# LB_BIT_i15_LIGHTTRIGGER-v02_rev1.net
KiCad netlist of a schematic drawn in EAGLE
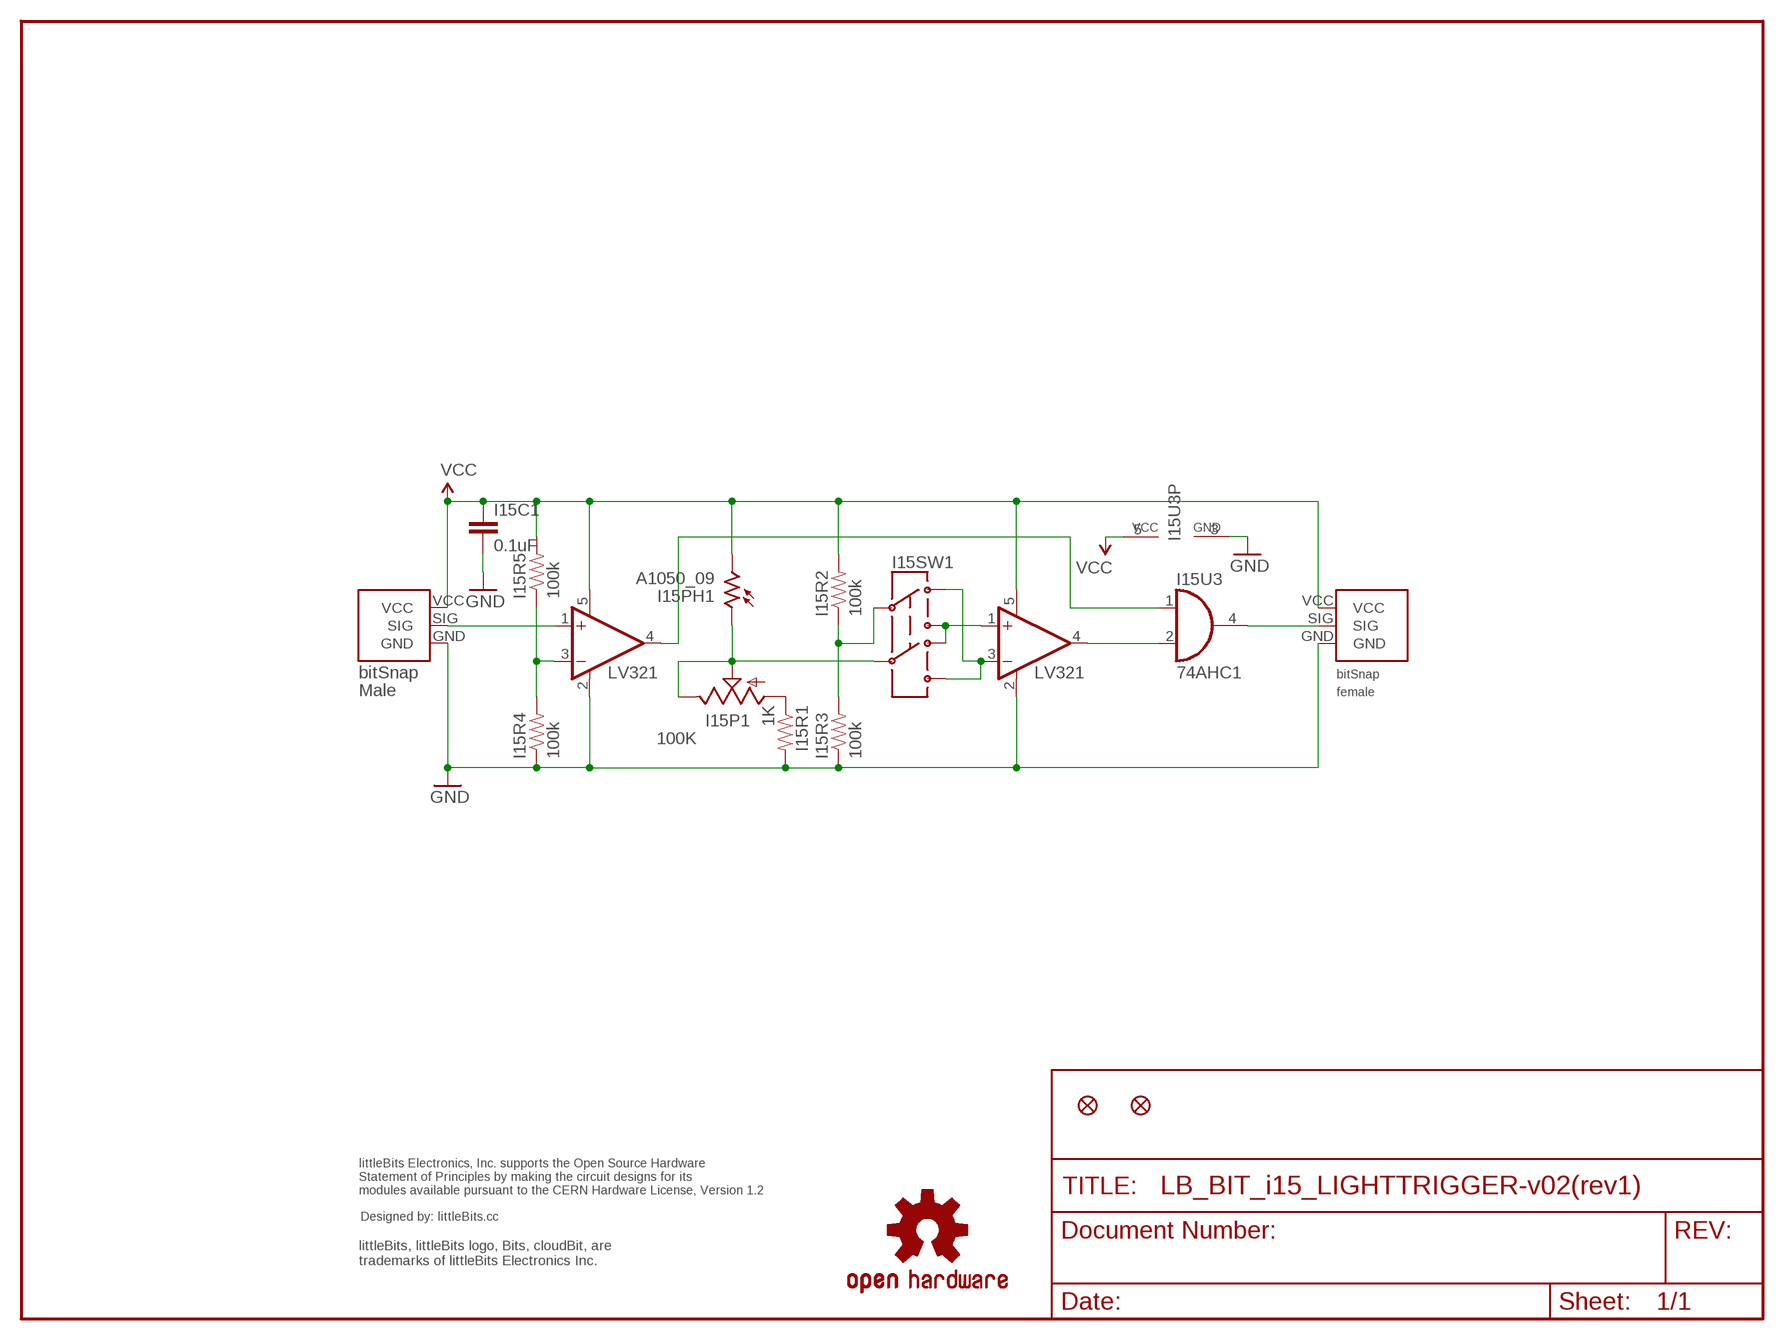
[diagram p0: schematic, sheet 1]

(export (version "E")
  (design (tool "Eeschema 10.0.6"))
  (components
    (comp (ref "I15BSF")
      (value "BITSNAP_FEMALE")
      (footprint "eagle-import:BITSNAP_FEMALE")
      (libsource (lib "eagle-import") (part "BITSNAP_FEMALE"))
    )
    (comp (ref "I15BSM")
      (value "BITSNAP_MALE")
      (footprint "eagle-import:BITSNAP_MALE")
      (libsource (lib "eagle-import") (part "BITSNAP_MALE"))
    )
    (comp (ref "I15C1")
      (value "0.1uF")
      (footprint "eagle-import:0603-CAP")
      (libsource (lib "eagle-import") (part "CAP0603-CAP"))
    )
    (comp (ref "I15FD1")
      (value "FIDUCIAL1X2")
      (footprint "eagle-import:FIDUCIAL-1X2")
      (libsource (lib "eagle-import") (part "FIDUCIAL1X2"))
    )
    (comp (ref "I15FD2")
      (value "FIDUCIAL1X2")
      (footprint "eagle-import:FIDUCIAL-1X2")
      (libsource (lib "eagle-import") (part "FIDUCIAL1X2"))
    )
    (comp (ref "I15P1")
      (value "POT-TRIM-SMD-BOURNS-3303")
      (footprint "eagle-import:POT-TRIM-SMD-BOURNS-3303")
      (libsource (lib "eagle-import") (part "POT-TRIM-SMD-BOURNS-3303"))
    )
    (comp (ref "I15PH1")
      (value "A1050_09")
      (footprint "eagle-import:T0-46-A10XX")
      (libsource (lib "eagle-import") (part "A1050_09"))
    )
    (comp (ref "I15R1")
      (value "1K")
      (footprint "eagle-import:0603-RES")
      (libsource (lib "eagle-import") (part "RESISTOR0603-RES"))
    )
    (comp (ref "I15R2")
      (value "100k")
      (footprint "eagle-import:0603-RES")
      (libsource (lib "eagle-import") (part "RESISTOR0603-RES"))
    )
    (comp (ref "I15R3")
      (value "100k")
      (footprint "eagle-import:0603-RES")
      (libsource (lib "eagle-import") (part "RESISTOR0603-RES"))
    )
    (comp (ref "I15R4")
      (value "100k")
      (footprint "eagle-import:0603-RES")
      (libsource (lib "eagle-import") (part "RESISTOR0603-RES"))
    )
    (comp (ref "I15R5")
      (value "100k")
      (footprint "eagle-import:0603-RES")
      (libsource (lib "eagle-import") (part "RESISTOR0603-RES"))
    )
    (comp (ref "I15SW1")
      (value "SWITCH-DPDTSMD")
      (footprint "eagle-import:AYZ0202")
      (libsource (lib "eagle-import") (part "SWITCH-DPDTSMD"))
    )
    (comp (ref "I15U1")
      (value "LV321")
      (footprint "eagle-import:SC70")
      (libsource (lib "eagle-import") (part "LV321"))
    )
    (comp (ref "I15U2")
      (value "LV321")
      (footprint "eagle-import:SC70")
      (libsource (lib "eagle-import") (part "LV321"))
    )
    (comp (ref "I15U3")
      (value "74AHC1")
      (footprint "eagle-import:SOT23-5")
      (libsource (lib "eagle-import") (part "741G08DBVLVC"))
    )
    (comp (ref "U$6")
      (value "OSHW-LOGOL")
      (footprint "eagle-import:OSHW-LOGO-L")
      (libsource (lib "eagle-import") (part "OSHW-LOGOL"))
    )
    (comp (ref "U$7")
      (value "OSHWCREDIT")
      (footprint "eagle-import:OSHWCREDIT")
      (libsource (lib "eagle-import") (part "OSHWCREDIT"))
    )
  )
  (nets
    (net (code "1") (name "GND") (class "Default")
      (node (ref "I15BSF") (pin "GND") (pinfunction "GND_GND") (pintype "bidirectional"))
      (node (ref "I15BSM") (pin "GND") (pinfunction "GND_GND") (pintype "bidirectional"))
      (node (ref "I15C1") (pin "2") (pinfunction "2_2") (pintype "passive"))
      (node (ref "I15R1") (pin "2") (pinfunction "2_2") (pintype "passive"))
      (node (ref "I15R3") (pin "1") (pinfunction "1_1") (pintype "passive"))
      (node (ref "I15R4") (pin "1") (pinfunction "1_1") (pintype "passive"))
      (node (ref "I15U1") (pin "2") (pinfunction "V-_2") (pintype "power_in"))
      (node (ref "I15U2") (pin "2") (pinfunction "V-_2") (pintype "power_in"))
      (node (ref "I15U3") (pin "3") (pinfunction "GND_3") (pintype "power_in"))
    )
    (net (code "2") (name "Net-(I15P1-A)") (class "Default")
      (node (ref "I15P1") (pin "1") (pinfunction "A_1") (pintype "passive"))
      (node (ref "I15R1") (pin "1") (pinfunction "1_1") (pintype "passive"))
    )
    (net (code "3") (name "Net-(I15P1-E)") (class "Default")
      (node (ref "I15P1") (pin "2") (pinfunction "S_2") (pintype "passive"))
      (node (ref "I15P1") (pin "3") (pinfunction "E_3") (pintype "passive"))
      (node (ref "I15PH1") (pin "1") (pinfunction "1_1") (pintype "passive"))
      (node (ref "I15SW1") (pin "5") (pinfunction "5_5") (pintype "bidirectional"))
    )
    (net (code "4") (name "Net-(I15R2-Pad1)") (class "Default")
      (node (ref "I15R2") (pin "1") (pinfunction "1_1") (pintype "passive"))
      (node (ref "I15R3") (pin "2") (pinfunction "2_2") (pintype "passive"))
      (node (ref "I15SW1") (pin "2") (pinfunction "2_2") (pintype "bidirectional"))
    )
    (net (code "5") (name "Net-(I15U1-+IN)") (class "Default")
      (node (ref "I15BSM") (pin "SIG") (pinfunction "SIG_SIG") (pintype "bidirectional"))
      (node (ref "I15U1") (pin "1") (pinfunction "+IN_1") (pintype "input"))
    )
    (net (code "6") (name "Net-(I15U1--IN)") (class "Default")
      (node (ref "I15R4") (pin "2") (pinfunction "2_2") (pintype "passive"))
      (node (ref "I15R5") (pin "1") (pinfunction "1_1") (pintype "passive"))
      (node (ref "I15U1") (pin "3") (pinfunction "-IN_3") (pintype "input"))
    )
    (net (code "7") (name "Net-(I15U1-OUT)") (class "Default")
      (node (ref "I15U1") (pin "4") (pinfunction "OUT_4") (pintype "output"))
      (node (ref "I15U3") (pin "1") (pinfunction "I0_1") (pintype "input"))
    )
    (net (code "8") (name "Net-(I15U2-+IN)") (class "Default")
      (node (ref "I15SW1") (pin "3") (pinfunction "3_3") (pintype "bidirectional"))
      (node (ref "I15SW1") (pin "4") (pinfunction "4_4") (pintype "bidirectional"))
      (node (ref "I15U2") (pin "1") (pinfunction "+IN_1") (pintype "input"))
    )
    (net (code "9") (name "Net-(I15U2--IN)") (class "Default")
      (node (ref "I15SW1") (pin "1") (pinfunction "1_1") (pintype "bidirectional"))
      (node (ref "I15SW1") (pin "6") (pinfunction "6_6") (pintype "bidirectional"))
      (node (ref "I15U2") (pin "3") (pinfunction "-IN_3") (pintype "input"))
    )
    (net (code "10") (name "Net-(I15U2-OUT)") (class "Default")
      (node (ref "I15U2") (pin "4") (pinfunction "OUT_4") (pintype "output"))
      (node (ref "I15U3") (pin "2") (pinfunction "I1_2") (pintype "input"))
    )
    (net (code "11") (name "Net-(I15U3A-O)") (class "Default")
      (node (ref "I15BSF") (pin "SIG") (pinfunction "SIG_SIG") (pintype "bidirectional"))
      (node (ref "I15U3") (pin "4") (pinfunction "O_4") (pintype "output"))
    )
    (net (code "12") (name "VCC") (class "Default")
      (node (ref "I15BSF") (pin "VCC") (pinfunction "VCC_VCC") (pintype "bidirectional"))
      (node (ref "I15BSM") (pin "VCC") (pinfunction "VCC_VCC") (pintype "bidirectional"))
      (node (ref "I15C1") (pin "1") (pinfunction "1_1") (pintype "passive"))
      (node (ref "I15PH1") (pin "2") (pinfunction "2_2") (pintype "passive"))
      (node (ref "I15R2") (pin "2") (pinfunction "2_2") (pintype "passive"))
      (node (ref "I15R5") (pin "2") (pinfunction "2_2") (pintype "passive"))
      (node (ref "I15U1") (pin "5") (pinfunction "V+_5") (pintype "power_in"))
      (node (ref "I15U2") (pin "5") (pinfunction "V+_5") (pintype "power_in"))
      (node (ref "I15U3") (pin "5") (pinfunction "VCC_5") (pintype "power_in"))
    )
  )
)
